# Lamp_Logic_Board_22_Power_2.net
KiCad netlist of a schematic drawn in EAGLE
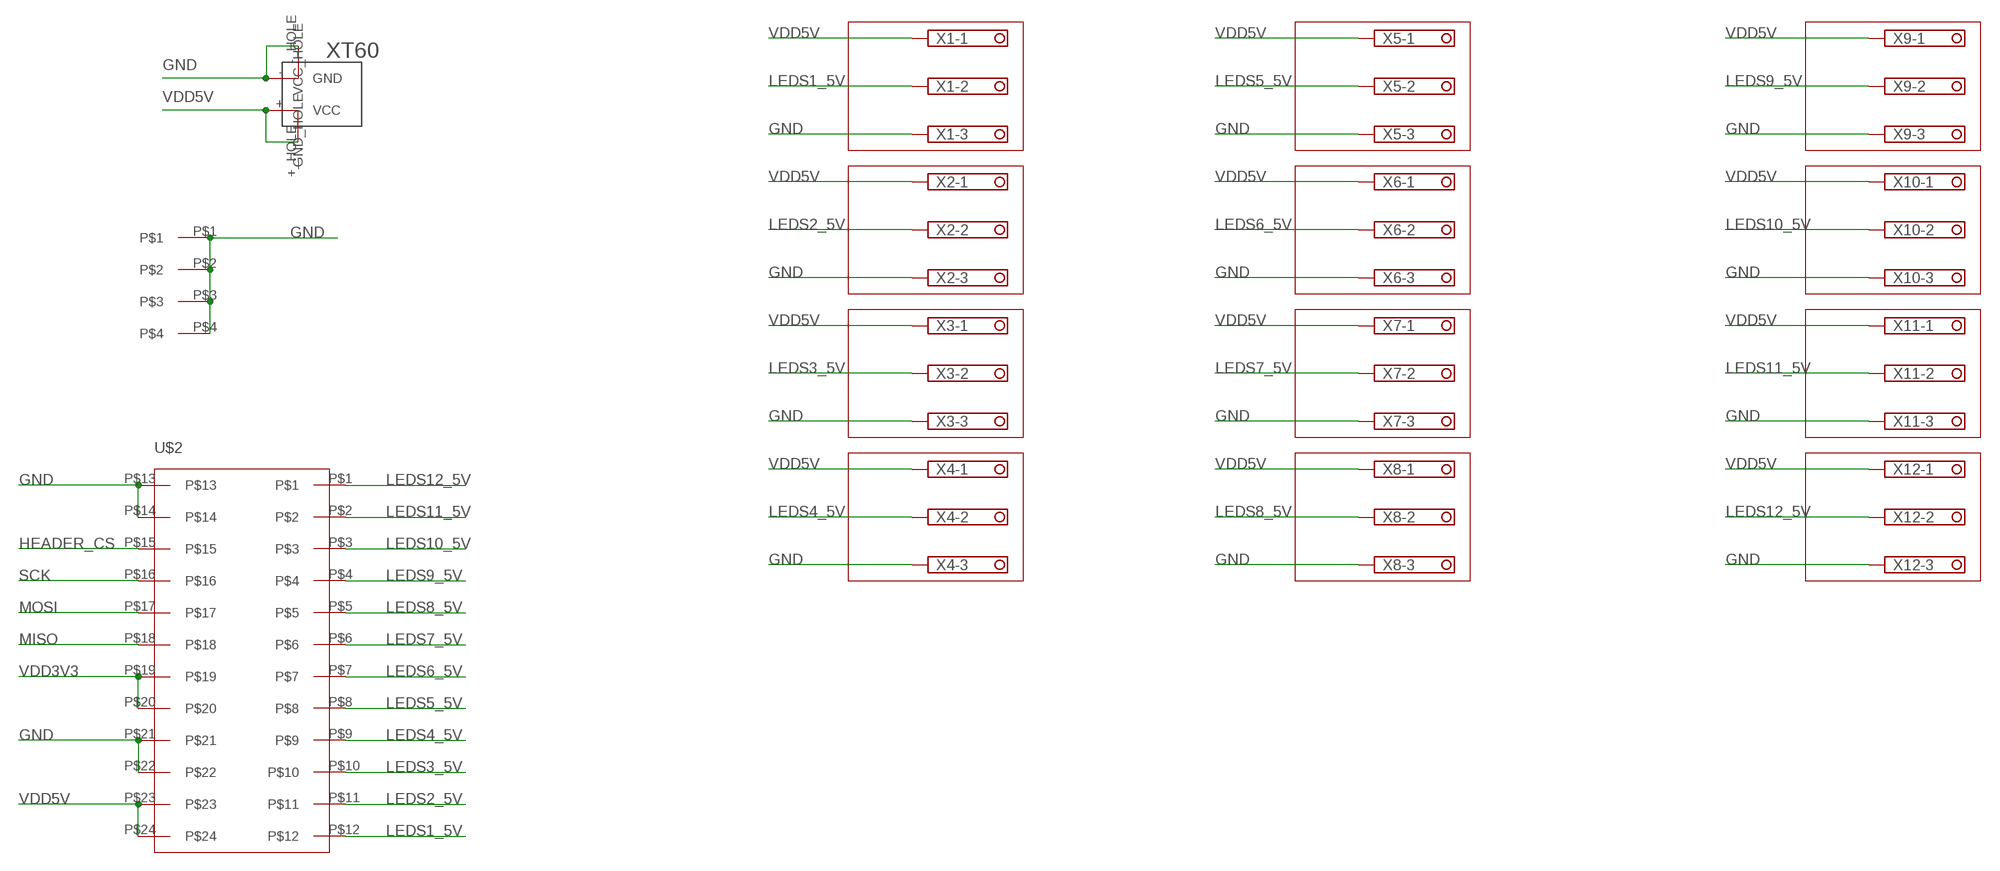
[diagram p0: schematic, sheet 1]

(export (version "E")
  (design (tool "Eeschema 10.0.6"))
  (components
    (comp (ref "U$1")
      (value "POWERBOARD_TEMPLATEPOWERBOARD_TEMPLATE")
      (footprint "eagle-import:4,PIECE")
      (libsource (lib "eagle-import") (part "POWERBOARD_TEMPLATEPOWERBOARD_TEMPLATE"))
    )
    (comp (ref "U$2")
      (value "MY_HEADER")
      (footprint "eagle-import:MY_HEADER")
      (libsource (lib "eagle-import") (part "MY_HEADER"))
    )
    (comp (ref "U$3")
      (value "XT60")
      (footprint "eagle-import:XT60")
      (libsource (lib "eagle-import") (part "XT60"))
    )
    (comp (ref "X1")
      (value "TERMINAL-BLOCK-3.5MM-3-PIN-LONG-PAD")
      (footprint "eagle-import:TERMINAL-BLOCK-3-PIN-3.5MM-LONG-PAD")
      (libsource (lib "eagle-import") (part "TERMINAL-BLOCK-3.5MM-3-PIN-LONG-PAD"))
    )
    (comp (ref "X2")
      (value "TERMINAL-BLOCK-3.5MM-3-PIN-LONG-PAD")
      (footprint "eagle-import:TERMINAL-BLOCK-3-PIN-3.5MM-LONG-PAD")
      (libsource (lib "eagle-import") (part "TERMINAL-BLOCK-3.5MM-3-PIN-LONG-PAD"))
    )
    (comp (ref "X3")
      (value "TERMINAL-BLOCK-3.5MM-3-PIN-LONG-PAD")
      (footprint "eagle-import:TERMINAL-BLOCK-3-PIN-3.5MM-LONG-PAD")
      (libsource (lib "eagle-import") (part "TERMINAL-BLOCK-3.5MM-3-PIN-LONG-PAD"))
    )
    (comp (ref "X4")
      (value "TERMINAL-BLOCK-3.5MM-3-PIN-LONG-PAD")
      (footprint "eagle-import:TERMINAL-BLOCK-3-PIN-3.5MM-LONG-PAD")
      (libsource (lib "eagle-import") (part "TERMINAL-BLOCK-3.5MM-3-PIN-LONG-PAD"))
    )
    (comp (ref "X5")
      (value "TERMINAL-BLOCK-3.5MM-3-PIN-LONG-PAD")
      (footprint "eagle-import:TERMINAL-BLOCK-3-PIN-3.5MM-LONG-PAD")
      (libsource (lib "eagle-import") (part "TERMINAL-BLOCK-3.5MM-3-PIN-LONG-PAD"))
    )
    (comp (ref "X6")
      (value "TERMINAL-BLOCK-3.5MM-3-PIN-LONG-PAD")
      (footprint "eagle-import:TERMINAL-BLOCK-3-PIN-3.5MM-LONG-PAD")
      (libsource (lib "eagle-import") (part "TERMINAL-BLOCK-3.5MM-3-PIN-LONG-PAD"))
    )
    (comp (ref "X7")
      (value "TERMINAL-BLOCK-3.5MM-3-PIN-LONG-PAD")
      (footprint "eagle-import:TERMINAL-BLOCK-3-PIN-3.5MM-LONG-PAD")
      (libsource (lib "eagle-import") (part "TERMINAL-BLOCK-3.5MM-3-PIN-LONG-PAD"))
    )
    (comp (ref "X8")
      (value "TERMINAL-BLOCK-3.5MM-3-PIN-LONG-PAD")
      (footprint "eagle-import:TERMINAL-BLOCK-3-PIN-3.5MM-LONG-PAD")
      (libsource (lib "eagle-import") (part "TERMINAL-BLOCK-3.5MM-3-PIN-LONG-PAD"))
    )
    (comp (ref "X9")
      (value "TERMINAL-BLOCK-3.5MM-3-PIN-LONG-PAD")
      (footprint "eagle-import:TERMINAL-BLOCK-3-PIN-3.5MM-LONG-PAD")
      (libsource (lib "eagle-import") (part "TERMINAL-BLOCK-3.5MM-3-PIN-LONG-PAD"))
    )
    (comp (ref "X10")
      (value "TERMINAL-BLOCK-3.5MM-3-PIN-LONG-PAD")
      (footprint "eagle-import:TERMINAL-BLOCK-3-PIN-3.5MM-LONG-PAD")
      (libsource (lib "eagle-import") (part "TERMINAL-BLOCK-3.5MM-3-PIN-LONG-PAD"))
    )
    (comp (ref "X11")
      (value "TERMINAL-BLOCK-3.5MM-3-PIN-LONG-PAD")
      (footprint "eagle-import:TERMINAL-BLOCK-3-PIN-3.5MM-LONG-PAD")
      (libsource (lib "eagle-import") (part "TERMINAL-BLOCK-3.5MM-3-PIN-LONG-PAD"))
    )
    (comp (ref "X12")
      (value "TERMINAL-BLOCK-3.5MM-3-PIN-LONG-PAD")
      (footprint "eagle-import:TERMINAL-BLOCK-3-PIN-3.5MM-LONG-PAD")
      (libsource (lib "eagle-import") (part "TERMINAL-BLOCK-3.5MM-3-PIN-LONG-PAD"))
    )
  )
  (nets
    (net (code "1") (name "/GND") (class "Default")
      (node (ref "U$1") (pin "P$1") (pinfunction "P$1_P$1") (pintype "bidirectional"))
      (node (ref "U$1") (pin "P$2") (pinfunction "P$2_P$2") (pintype "bidirectional"))
      (node (ref "U$1") (pin "P$3") (pinfunction "P$3_P$3") (pintype "bidirectional"))
      (node (ref "U$1") (pin "P$4") (pinfunction "P$4_P$4") (pintype "bidirectional"))
      (node (ref "U$2") (pin "P$13") (pinfunction "P$13_P$13") (pintype "bidirectional"))
      (node (ref "U$2") (pin "P$14") (pinfunction "P$14_P$14") (pintype "bidirectional"))
      (node (ref "U$2") (pin "P$21") (pinfunction "P$21_P$21") (pintype "bidirectional"))
      (node (ref "U$2") (pin "P$22") (pinfunction "P$22_P$22") (pintype "bidirectional"))
      (node (ref "U$3") (pin "-") (pinfunction "GND_-") (pintype "bidirectional"))
      (node (ref "U$3") (pin "-_HOLE") (pinfunction "GND_HOLE_-_HOLE") (pintype "bidirectional"))
      (node (ref "X1") (pin "3") (pinfunction "K_3") (pintype "passive"))
      (node (ref "X10") (pin "3") (pinfunction "K_3") (pintype "passive"))
      (node (ref "X11") (pin "3") (pinfunction "K_3") (pintype "passive"))
      (node (ref "X12") (pin "3") (pinfunction "K_3") (pintype "passive"))
      (node (ref "X2") (pin "3") (pinfunction "K_3") (pintype "passive"))
      (node (ref "X3") (pin "3") (pinfunction "K_3") (pintype "passive"))
      (node (ref "X4") (pin "3") (pinfunction "K_3") (pintype "passive"))
      (node (ref "X5") (pin "3") (pinfunction "K_3") (pintype "passive"))
      (node (ref "X6") (pin "3") (pinfunction "K_3") (pintype "passive"))
      (node (ref "X7") (pin "3") (pinfunction "K_3") (pintype "passive"))
      (node (ref "X8") (pin "3") (pinfunction "K_3") (pintype "passive"))
      (node (ref "X9") (pin "3") (pinfunction "K_3") (pintype "passive"))
    )
    (net (code "2") (name "/HEADER_CS") (class "Default")
      (node (ref "U$2") (pin "P$15") (pinfunction "P$15_P$15") (pintype "bidirectional"))
    )
    (net (code "3") (name "/LEDS1_5V") (class "Default")
      (node (ref "U$2") (pin "P$12") (pinfunction "P$12_P$12") (pintype "bidirectional"))
      (node (ref "X1") (pin "2") (pinfunction "K_2") (pintype "passive"))
    )
    (net (code "4") (name "/LEDS2_5V") (class "Default")
      (node (ref "U$2") (pin "P$11") (pinfunction "P$11_P$11") (pintype "bidirectional"))
      (node (ref "X2") (pin "2") (pinfunction "K_2") (pintype "passive"))
    )
    (net (code "5") (name "/LEDS3_5V") (class "Default")
      (node (ref "U$2") (pin "P$10") (pinfunction "P$10_P$10") (pintype "bidirectional"))
      (node (ref "X3") (pin "2") (pinfunction "K_2") (pintype "passive"))
    )
    (net (code "6") (name "/LEDS4_5V") (class "Default")
      (node (ref "U$2") (pin "P$9") (pinfunction "P$9_P$9") (pintype "bidirectional"))
      (node (ref "X4") (pin "2") (pinfunction "K_2") (pintype "passive"))
    )
    (net (code "7") (name "/LEDS5_5V") (class "Default")
      (node (ref "U$2") (pin "P$8") (pinfunction "P$8_P$8") (pintype "bidirectional"))
      (node (ref "X5") (pin "2") (pinfunction "K_2") (pintype "passive"))
    )
    (net (code "8") (name "/LEDS6_5V") (class "Default")
      (node (ref "U$2") (pin "P$7") (pinfunction "P$7_P$7") (pintype "bidirectional"))
      (node (ref "X6") (pin "2") (pinfunction "K_2") (pintype "passive"))
    )
    (net (code "9") (name "/LEDS7_5V") (class "Default")
      (node (ref "U$2") (pin "P$6") (pinfunction "P$6_P$6") (pintype "bidirectional"))
      (node (ref "X7") (pin "2") (pinfunction "K_2") (pintype "passive"))
    )
    (net (code "10") (name "/LEDS8_5V") (class "Default")
      (node (ref "U$2") (pin "P$5") (pinfunction "P$5_P$5") (pintype "bidirectional"))
      (node (ref "X8") (pin "2") (pinfunction "K_2") (pintype "passive"))
    )
    (net (code "11") (name "/LEDS9_5V") (class "Default")
      (node (ref "U$2") (pin "P$4") (pinfunction "P$4_P$4") (pintype "bidirectional"))
      (node (ref "X9") (pin "2") (pinfunction "K_2") (pintype "passive"))
    )
    (net (code "12") (name "/LEDS10_5V") (class "Default")
      (node (ref "U$2") (pin "P$3") (pinfunction "P$3_P$3") (pintype "bidirectional"))
      (node (ref "X10") (pin "2") (pinfunction "K_2") (pintype "passive"))
    )
    (net (code "13") (name "/LEDS11_5V") (class "Default")
      (node (ref "U$2") (pin "P$2") (pinfunction "P$2_P$2") (pintype "bidirectional"))
      (node (ref "X11") (pin "2") (pinfunction "K_2") (pintype "passive"))
    )
    (net (code "14") (name "/LEDS12_5V") (class "Default")
      (node (ref "U$2") (pin "P$1") (pinfunction "P$1_P$1") (pintype "bidirectional"))
      (node (ref "X12") (pin "2") (pinfunction "K_2") (pintype "passive"))
    )
    (net (code "15") (name "/MISO") (class "Default")
      (node (ref "U$2") (pin "P$18") (pinfunction "P$18_P$18") (pintype "bidirectional"))
    )
    (net (code "16") (name "/MOSI") (class "Default")
      (node (ref "U$2") (pin "P$17") (pinfunction "P$17_P$17") (pintype "bidirectional"))
    )
    (net (code "17") (name "/SCK") (class "Default")
      (node (ref "U$2") (pin "P$16") (pinfunction "P$16_P$16") (pintype "bidirectional"))
    )
    (net (code "18") (name "/VDD3V3") (class "Default")
      (node (ref "U$2") (pin "P$19") (pinfunction "P$19_P$19") (pintype "bidirectional"))
      (node (ref "U$2") (pin "P$20") (pinfunction "P$20_P$20") (pintype "bidirectional"))
    )
    (net (code "19") (name "/VDD5V") (class "Default")
      (node (ref "U$2") (pin "P$23") (pinfunction "P$23_P$23") (pintype "bidirectional"))
      (node (ref "U$2") (pin "P$24") (pinfunction "P$24_P$24") (pintype "bidirectional"))
      (node (ref "U$3") (pin "+") (pinfunction "VCC_+") (pintype "bidirectional"))
      (node (ref "U$3") (pin "+_HOLE") (pinfunction "VCC_HOLE_+_HOLE") (pintype "bidirectional"))
      (node (ref "X1") (pin "1") (pinfunction "K_1") (pintype "passive"))
      (node (ref "X10") (pin "1") (pinfunction "K_1") (pintype "passive"))
      (node (ref "X11") (pin "1") (pinfunction "K_1") (pintype "passive"))
      (node (ref "X12") (pin "1") (pinfunction "K_1") (pintype "passive"))
      (node (ref "X2") (pin "1") (pinfunction "K_1") (pintype "passive"))
      (node (ref "X3") (pin "1") (pinfunction "K_1") (pintype "passive"))
      (node (ref "X4") (pin "1") (pinfunction "K_1") (pintype "passive"))
      (node (ref "X5") (pin "1") (pinfunction "K_1") (pintype "passive"))
      (node (ref "X6") (pin "1") (pinfunction "K_1") (pintype "passive"))
      (node (ref "X7") (pin "1") (pinfunction "K_1") (pintype "passive"))
      (node (ref "X8") (pin "1") (pinfunction "K_1") (pintype "passive"))
      (node (ref "X9") (pin "1") (pinfunction "K_1") (pintype "passive"))
    )
  )
)
